# atx_breakout.net
KiCad netlist of a schematic drawn in EAGLE
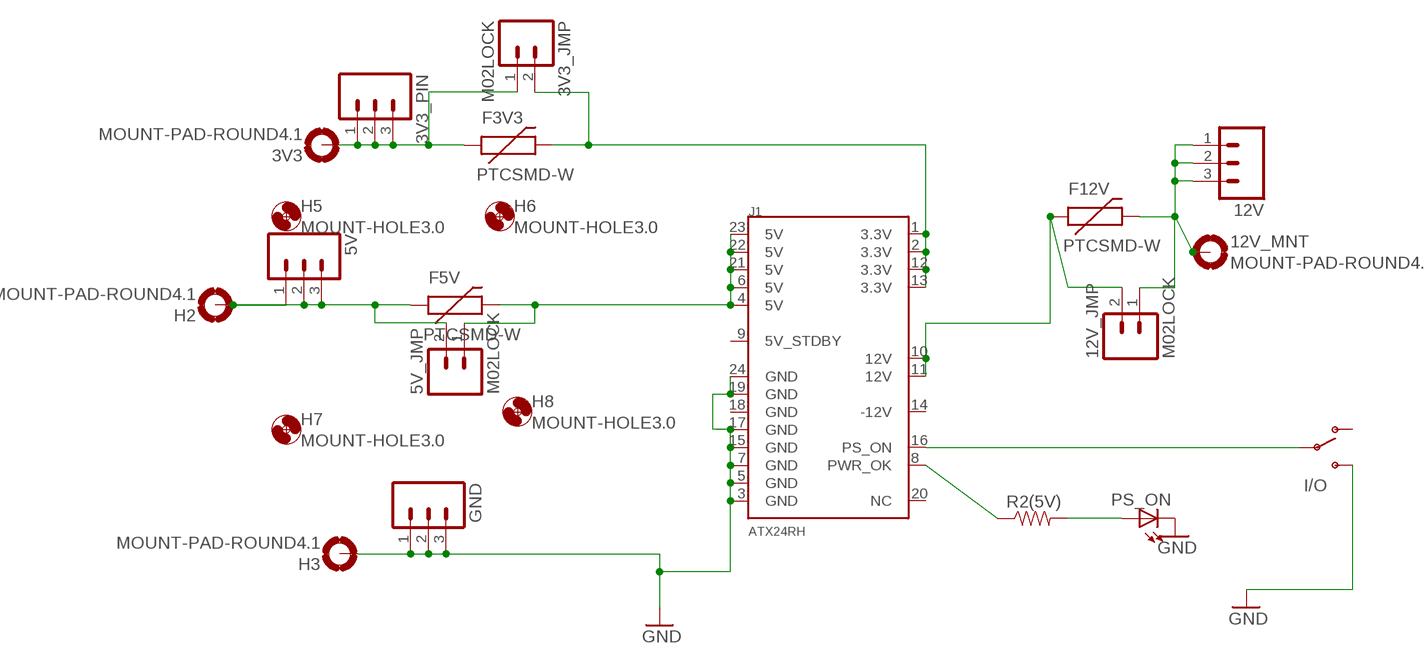
[diagram p0: schematic, sheet 1]

(export (version "E")
  (design (tool "Eeschema 10.0.6"))
  (components
    (comp (ref "3V3")
      (value "MOUNT-PAD-ROUND4.1")
      (footprint "eagle-import:4,1-PAD")
      (libsource (lib "eagle-import") (part "MOUNT-PAD-ROUND4.1"))
    )
    (comp (ref "3V3_JMP")
      (value "M02LOCK")
      (footprint "eagle-import:1X02_LOCK")
      (libsource (lib "eagle-import") (part "M02LOCK"))
    )
    (comp (ref "3V3_PIN")
      (value "M031X03_NO_SILK")
      (footprint "eagle-import:1X03_NO_SILK")
      (libsource (lib "eagle-import") (part "M031X03_NO_SILK"))
    )
    (comp (ref "5V")
      (value "M031X03_NO_SILK")
      (footprint "eagle-import:1X03_NO_SILK")
      (libsource (lib "eagle-import") (part "M031X03_NO_SILK"))
    )
    (comp (ref "5V_JMP")
      (value "M02LOCK")
      (footprint "eagle-import:1X02_LOCK")
      (libsource (lib "eagle-import") (part "M02LOCK"))
    )
    (comp (ref "12V")
      (value "M031X03_NO_SILK")
      (footprint "eagle-import:1X03_NO_SILK")
      (libsource (lib "eagle-import") (part "M031X03_NO_SILK"))
    )
    (comp (ref "12V_JMP")
      (value "M02LOCK")
      (footprint "eagle-import:1X02_LOCK")
      (libsource (lib "eagle-import") (part "M02LOCK"))
    )
    (comp (ref "12V_MNT")
      (value "MOUNT-PAD-ROUND4.1")
      (footprint "eagle-import:4,1-PAD")
      (libsource (lib "eagle-import") (part "MOUNT-PAD-ROUND4.1"))
    )
    (comp (ref "F3V3")
      (value "PTCSMD-W")
      (footprint "eagle-import:PTC-1206-WIDE")
      (libsource (lib "eagle-import") (part "PTCSMD-W"))
    )
    (comp (ref "F5V")
      (value "PTCSMD-W")
      (footprint "eagle-import:PTC-1206-WIDE")
      (libsource (lib "eagle-import") (part "PTCSMD-W"))
    )
    (comp (ref "F12V")
      (value "PTCSMD-W")
      (footprint "eagle-import:PTC-1206-WIDE")
      (libsource (lib "eagle-import") (part "PTCSMD-W"))
    )
    (comp (ref "GND")
      (value "M031X03_NO_SILK")
      (footprint "eagle-import:1X03_NO_SILK")
      (libsource (lib "eagle-import") (part "M031X03_NO_SILK"))
    )
    (comp (ref "H2")
      (value "MOUNT-PAD-ROUND4.1")
      (footprint "eagle-import:4,1-PAD")
      (libsource (lib "eagle-import") (part "MOUNT-PAD-ROUND4.1"))
    )
    (comp (ref "H3")
      (value "MOUNT-PAD-ROUND4.1")
      (footprint "eagle-import:4,1-PAD")
      (libsource (lib "eagle-import") (part "MOUNT-PAD-ROUND4.1"))
    )
    (comp (ref "H5")
      (value "MOUNT-HOLE3.0")
      (footprint "eagle-import:3,0")
      (libsource (lib "eagle-import") (part "MOUNT-HOLE3.0"))
    )
    (comp (ref "H6")
      (value "MOUNT-HOLE3.0")
      (footprint "eagle-import:3,0")
      (libsource (lib "eagle-import") (part "MOUNT-HOLE3.0"))
    )
    (comp (ref "H7")
      (value "MOUNT-HOLE3.0")
      (footprint "eagle-import:3,0")
      (libsource (lib "eagle-import") (part "MOUNT-HOLE3.0"))
    )
    (comp (ref "H8")
      (value "MOUNT-HOLE3.0")
      (footprint "eagle-import:3,0")
      (libsource (lib "eagle-import") (part "MOUNT-HOLE3.0"))
    )
    (comp (ref "I/O")
      (value "SWITCH-SPDTPTH")
      (footprint "eagle-import:SWITCH-SPDT")
      (libsource (lib "eagle-import") (part "SWITCH-SPDTPTH"))
    )
    (comp (ref "J1")
      (value "ATX24RH")
      (footprint "eagle-import:ATX24_RIGHT_ANGLE")
      (libsource (lib "eagle-import") (part "ATX24RH"))
    )
    (comp (ref "PS_ON")
      (value "LED-3MM-NO_SILK")
      (footprint "eagle-import:LED3MM-NS")
      (libsource (lib "eagle-import") (part "LED-3MM-NO_SILK"))
    )
    (comp (ref "R2(5V)")
      (value "RESISTORAXIAL-0.3")
      (footprint "eagle-import:AXIAL-0.3")
      (libsource (lib "eagle-import") (part "RESISTORAXIAL-0.3"))
    )
  )
  (nets
    (net (code "1") (name "GND") (class "Default")
      (node (ref "GND") (pin "1") (pinfunction "1_1") (pintype "passive"))
      (node (ref "GND") (pin "2") (pinfunction "2_2") (pintype "passive"))
      (node (ref "GND") (pin "3") (pinfunction "3_3") (pintype "passive"))
      (node (ref "H3") (pin "B4,1") (pinfunction "MOUNT_B4,1") (pintype "passive"))
      (node (ref "I/O") (pin "3") (pinfunction "S_3") (pintype "passive"))
      (node (ref "J1") (pin "15") (pinfunction "GND_15") (pintype "bidirectional"))
      (node (ref "J1") (pin "17") (pinfunction "GND_17") (pintype "bidirectional"))
      (node (ref "J1") (pin "19") (pinfunction "GND_19") (pintype "bidirectional"))
      (node (ref "J1") (pin "24") (pinfunction "GND_24") (pintype "bidirectional"))
      (node (ref "J1") (pin "3") (pinfunction "GND_3") (pintype "bidirectional"))
      (node (ref "J1") (pin "5") (pinfunction "GND_5") (pintype "bidirectional"))
      (node (ref "J1") (pin "7") (pinfunction "GND_7") (pintype "bidirectional"))
      (node (ref "PS_ON") (pin "K") (pinfunction "C_K") (pintype "passive"))
    )
    (net (code "2") (name "Net-(3V3-MOUNT)") (class "Default")
      (node (ref "3V3") (pin "B4,1") (pinfunction "MOUNT_B4,1") (pintype "passive"))
      (node (ref "3V3_JMP") (pin "1") (pinfunction "1_1") (pintype "passive"))
      (node (ref "3V3_PIN") (pin "1") (pinfunction "1_1") (pintype "passive"))
      (node (ref "3V3_PIN") (pin "2") (pinfunction "2_2") (pintype "passive"))
      (node (ref "3V3_PIN") (pin "3") (pinfunction "3_3") (pintype "passive"))
      (node (ref "F3V3") (pin "1") (pinfunction "1_1") (pintype "bidirectional"))
    )
    (net (code "3") (name "Net-(3V3_JMP-Pad2)") (class "Default")
      (node (ref "3V3_JMP") (pin "2") (pinfunction "2_2") (pintype "passive"))
      (node (ref "F3V3") (pin "2") (pinfunction "2_2") (pintype "bidirectional"))
      (node (ref "J1") (pin "1") (pinfunction "3.3V_1") (pintype "bidirectional"))
      (node (ref "J1") (pin "12") (pinfunction "3.3V_12") (pintype "bidirectional"))
      (node (ref "J1") (pin "13") (pinfunction "3.3V_13") (pintype "bidirectional"))
      (node (ref "J1") (pin "2") (pinfunction "3.3V_2") (pintype "bidirectional"))
    )
    (net (code "4") (name "Net-(5V_JMP-Pad1)") (class "Default")
      (node (ref "5V_JMP") (pin "1") (pinfunction "1_1") (pintype "passive"))
      (node (ref "F5V") (pin "2") (pinfunction "2_2") (pintype "bidirectional"))
      (node (ref "J1") (pin "21") (pinfunction "5V_21") (pintype "bidirectional"))
      (node (ref "J1") (pin "22") (pinfunction "5V_22") (pintype "bidirectional"))
      (node (ref "J1") (pin "23") (pinfunction "5V_23") (pintype "bidirectional"))
      (node (ref "J1") (pin "4") (pinfunction "5V_4") (pintype "bidirectional"))
      (node (ref "J1") (pin "6") (pinfunction "5V_6") (pintype "bidirectional"))
    )
    (net (code "5") (name "Net-(12V_JMP-Pad2)") (class "Default")
      (node (ref "12V_JMP") (pin "2") (pinfunction "2_2") (pintype "passive"))
      (node (ref "F12V") (pin "1") (pinfunction "1_1") (pintype "bidirectional"))
      (node (ref "J1") (pin "10") (pinfunction "12V_10") (pintype "bidirectional"))
      (node (ref "J1") (pin "11") (pinfunction "12V_11") (pintype "bidirectional"))
    )
    (net (code "6") (name "Net-(12V_MNT-MOUNT)") (class "Default")
      (node (ref "12V") (pin "1") (pinfunction "1_1") (pintype "passive"))
      (node (ref "12V") (pin "2") (pinfunction "2_2") (pintype "passive"))
      (node (ref "12V") (pin "3") (pinfunction "3_3") (pintype "passive"))
      (node (ref "12V_JMP") (pin "1") (pinfunction "1_1") (pintype "passive"))
      (node (ref "12V_MNT") (pin "B4,1") (pinfunction "MOUNT_B4,1") (pintype "passive"))
      (node (ref "F12V") (pin "2") (pinfunction "2_2") (pintype "bidirectional"))
    )
    (net (code "7") (name "Net-(H2-MOUNT)") (class "Default")
      (node (ref "5V") (pin "1") (pinfunction "1_1") (pintype "passive"))
      (node (ref "5V") (pin "2") (pinfunction "2_2") (pintype "passive"))
      (node (ref "5V") (pin "3") (pinfunction "3_3") (pintype "passive"))
      (node (ref "5V_JMP") (pin "2") (pinfunction "2_2") (pintype "passive"))
      (node (ref "F5V") (pin "1") (pinfunction "1_1") (pintype "bidirectional"))
      (node (ref "H2") (pin "B4,1") (pinfunction "MOUNT_B4,1") (pintype "passive"))
    )
    (net (code "8") (name "Net-(I/O-P)") (class "Default")
      (node (ref "I/O") (pin "2") (pinfunction "P_2") (pintype "passive"))
      (node (ref "J1") (pin "16") (pinfunction "PS_ON_16") (pintype "bidirectional"))
    )
    (net (code "9") (name "Net-(J1-PWR_OK)") (class "Default")
      (node (ref "J1") (pin "8") (pinfunction "PWR_OK_8") (pintype "bidirectional"))
      (node (ref "R2(5V)") (pin "P$1") (pinfunction "1_P$1") (pintype "passive"))
    )
    (net (code "10") (name "Net-(R2(5V)-2)") (class "Default")
      (node (ref "PS_ON") (pin "A") (pinfunction "A_A") (pintype "passive"))
      (node (ref "R2(5V)") (pin "P$2") (pinfunction "2_P$2") (pintype "passive"))
    )
    (net (code "11") (name "unconnected-(I/O-O-Pad1)") (class "Default")
      (node (ref "I/O") (pin "1") (pinfunction "O_1") (pintype "passive"))
    )
    (net (code "12") (name "unconnected-(J1--12V-Pad14)") (class "Default")
      (node (ref "J1") (pin "14") (pinfunction "-12V_14") (pintype "bidirectional"))
    )
    (net (code "13") (name "unconnected-(J1-5V_STDBY-Pad9)") (class "Default")
      (node (ref "J1") (pin "9") (pinfunction "5V_STDBY_9") (pintype "bidirectional"))
    )
    (net (code "14") (name "unconnected-(J1-GND-Pad18)") (class "Default")
      (node (ref "J1") (pin "18") (pinfunction "GND_18") (pintype "bidirectional"))
    )
    (net (code "15") (name "unconnected-(J1-NC-Pad20)") (class "Default")
      (node (ref "J1") (pin "20") (pinfunction "NC_20") (pintype "bidirectional"))
    )
  )
)
